# PMM_R_19.net
KiCad netlist of a schematic drawn in EAGLE
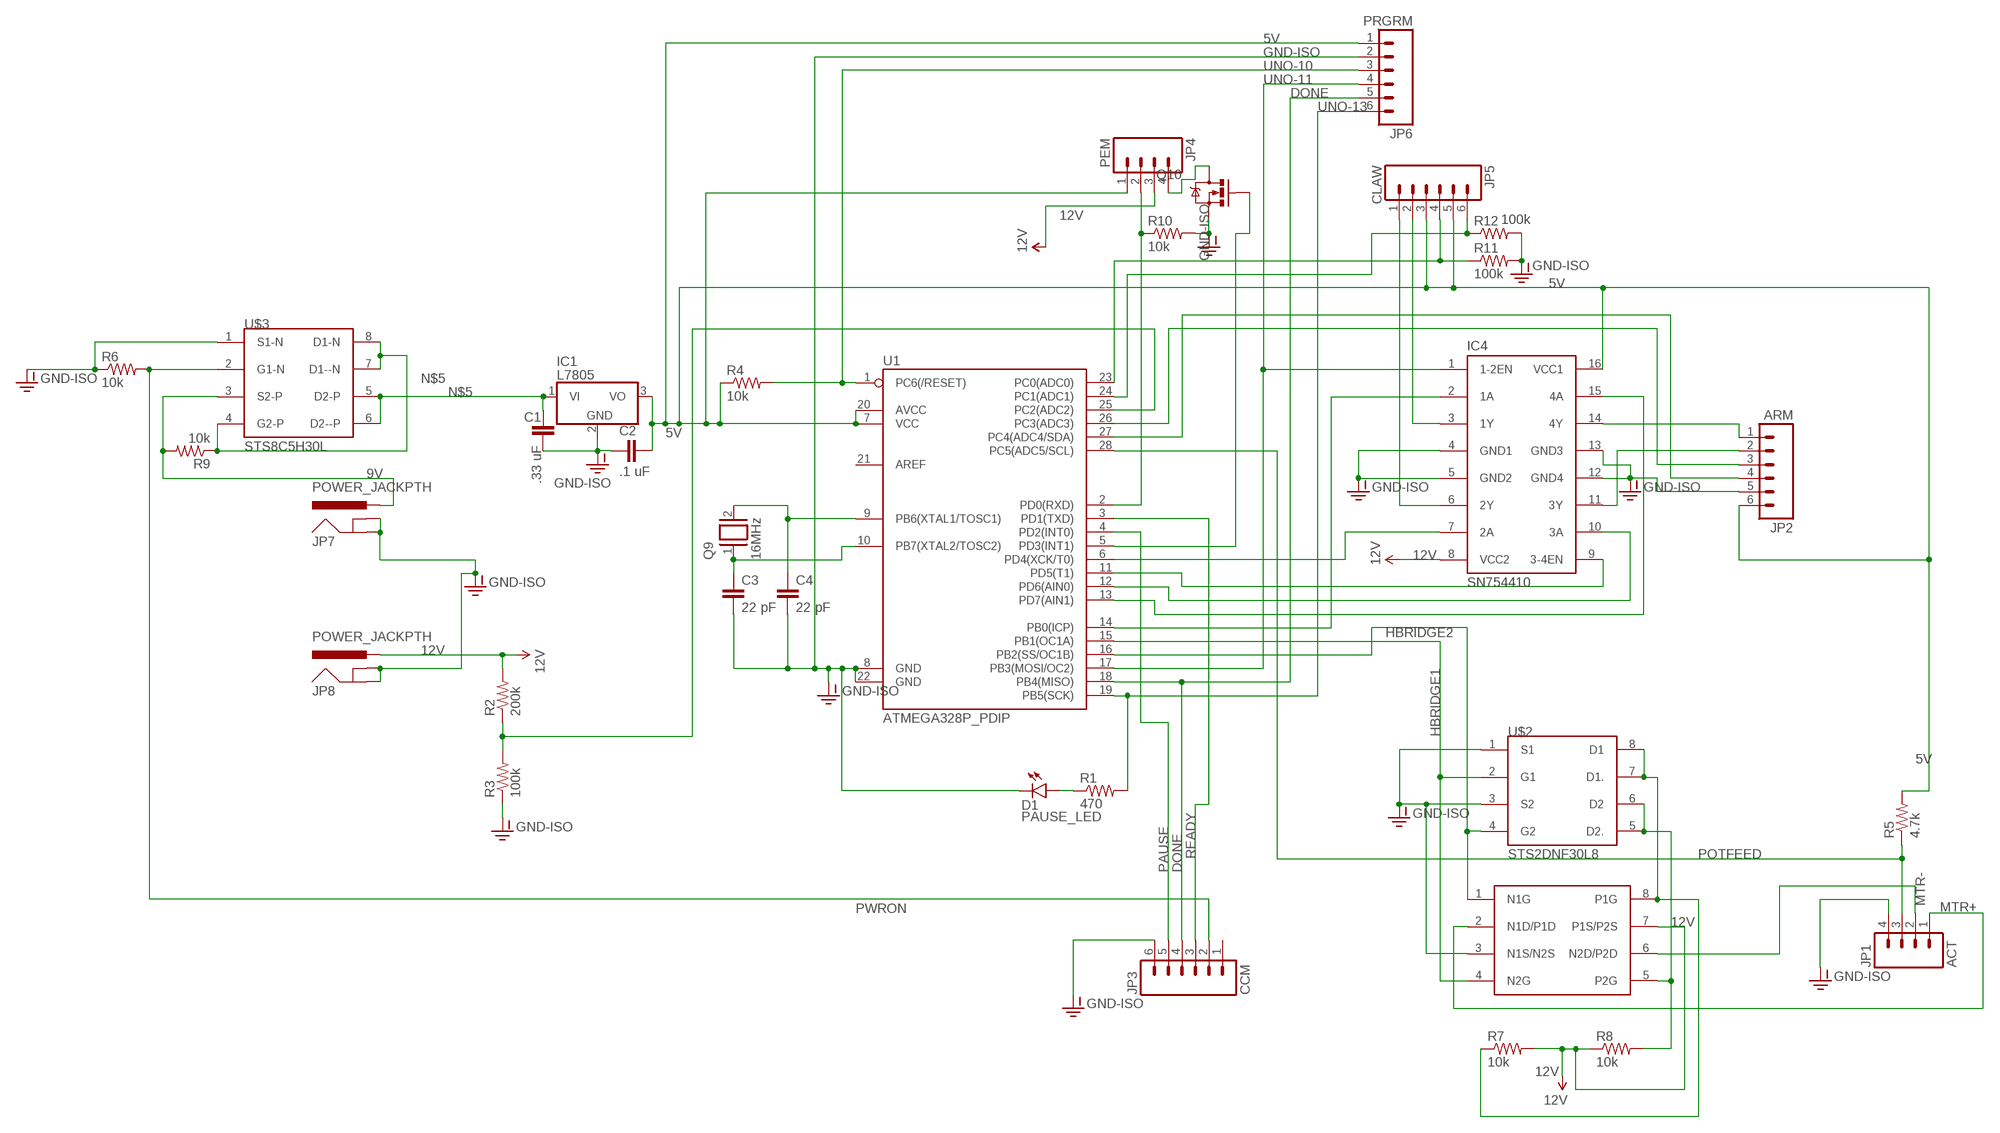
[diagram p0: schematic, sheet 1]

(export (version "E")
  (design (tool "Eeschema 10.0.6"))
  (components
    (comp (ref "C1")
      (value ".33 uF")
      (footprint "eagle-import:CAP-PTH-SMALL-KIT")
      (libsource (lib "eagle-import") (part "CAPKIT"))
    )
    (comp (ref "C2")
      (value ".1 uF")
      (footprint "eagle-import:CAP-PTH-SMALL-KIT")
      (libsource (lib "eagle-import") (part "CAPKIT"))
    )
    (comp (ref "C3")
      (value "22 pF")
      (footprint "eagle-import:C2.5-3")
      (libsource (lib "eagle-import") (part "C2,5-3"))
    )
    (comp (ref "C4")
      (value "22 pF")
      (footprint "eagle-import:C2.5-3")
      (libsource (lib "eagle-import") (part "C2,5-3"))
    )
    (comp (ref "D1")
      (value "PAUSE_LED")
      (footprint "eagle-import:LED5MM")
      (libsource (lib "eagle-import") (part "LED5MM"))
    )
    (comp (ref "DMHC3025LSD8")
      (value "DMHC3025LSD8")
      (footprint "eagle-import:SOIC-8")
      (libsource (lib "eagle-import") (part "DMHC3025LSD8"))
    )
    (comp (ref "IC1")
      (value "L7805")
      (footprint "eagle-import:TO220V")
      (libsource (lib "eagle-import") (part "78TV18"))
    )
    (comp (ref "IC4")
      (value "SN754410")
      (footprint "eagle-import:DIL16")
      (fields (field (name "MPN") "L293D"))
      (libsource (lib "eagle-import") (part "L293D"))
    )
    (comp (ref "JP1")
      (value "ACT")
      (footprint "eagle-import:1X04")
      (libsource (lib "eagle-import") (part "M04PTH"))
    )
    (comp (ref "JP2")
      (value "ARM")
      (footprint "eagle-import:1X06")
      (libsource (lib "eagle-import") (part "M06SILK_FEMALE_PTH"))
    )
    (comp (ref "JP3")
      (value "CCM")
      (footprint "eagle-import:1X06")
      (libsource (lib "eagle-import") (part "M06SILK_FEMALE_PTH"))
    )
    (comp (ref "JP4")
      (value "PEM")
      (footprint "eagle-import:1X04")
      (libsource (lib "eagle-import") (part "M04PTH"))
    )
    (comp (ref "JP5")
      (value "CLAW")
      (footprint "eagle-import:1X06")
      (libsource (lib "eagle-import") (part "M06SILK_FEMALE_PTH"))
    )
    (comp (ref "JP6")
      (value "PRGRM")
      (footprint "eagle-import:1X06")
      (libsource (lib "eagle-import") (part "M06SILK_FEMALE_PTH"))
    )
    (comp (ref "JP7")
      (value "POWER_JACKPTH")
      (footprint "eagle-import:POWER_JACK_PTH")
      (libsource (lib "eagle-import") (part "POWER_JACKPTH"))
    )
    (comp (ref "JP8")
      (value "POWER_JACKPTH")
      (footprint "eagle-import:POWER_JACK_PTH")
      (libsource (lib "eagle-import") (part "POWER_JACKPTH"))
    )
    (comp (ref "Q9")
      (value "16MHz")
      (footprint "eagle-import:QS")
      (libsource (lib "eagle-import") (part "XTAL/S"))
    )
    (comp (ref "Q10")
      (value "MOSFET-NCHANNELFQP30N06L")
      (footprint "eagle-import:TO220V")
      (libsource (lib "eagle-import") (part "MOSFET-NCHANNELFQP30N06L"))
    )
    (comp (ref "R1")
      (value "470")
      (footprint "eagle-import:1206")
      (libsource (lib "eagle-import") (part "RESISTOR1206"))
    )
    (comp (ref "R2")
      (value "200k")
      (footprint "eagle-import:1206")
      (libsource (lib "eagle-import") (part "RESISTOR1206"))
    )
    (comp (ref "R3")
      (value "100k")
      (footprint "eagle-import:1206")
      (libsource (lib "eagle-import") (part "RESISTOR1206"))
    )
    (comp (ref "R4")
      (value "10k")
      (footprint "eagle-import:1206")
      (libsource (lib "eagle-import") (part "RESISTOR1206"))
    )
    (comp (ref "R5")
      (value "4.7k")
      (footprint "eagle-import:1206")
      (libsource (lib "eagle-import") (part "RESISTOR1206"))
    )
    (comp (ref "R6")
      (value "10k")
      (footprint "eagle-import:1206")
      (libsource (lib "eagle-import") (part "RESISTOR1206"))
    )
    (comp (ref "R7")
      (value "10k")
      (footprint "eagle-import:1206")
      (libsource (lib "eagle-import") (part "RESISTOR1206"))
    )
    (comp (ref "R8")
      (value "10k")
      (footprint "eagle-import:1206")
      (libsource (lib "eagle-import") (part "RESISTOR1206"))
    )
    (comp (ref "R9")
      (value "10k")
      (footprint "eagle-import:1206")
      (libsource (lib "eagle-import") (part "RESISTOR1206"))
    )
    (comp (ref "R10")
      (value "10k")
      (footprint "eagle-import:1206")
      (libsource (lib "eagle-import") (part "RESISTOR1206"))
    )
    (comp (ref "R11")
      (value "100k")
      (footprint "eagle-import:1206")
      (libsource (lib "eagle-import") (part "RESISTOR1206"))
    )
    (comp (ref "R12")
      (value "100k")
      (footprint "eagle-import:1206")
      (libsource (lib "eagle-import") (part "RESISTOR1206"))
    )
    (comp (ref "U$2")
      (value "STS2DNF30L8")
      (footprint "eagle-import:SOIC-8")
      (libsource (lib "eagle-import") (part "STS2DNF30L8"))
    )
    (comp (ref "U$3")
      (value "STS8C5H30L")
      (footprint "eagle-import:SOIC-8")
      (libsource (lib "eagle-import") (part "STS8C5H30LSTS8C5H30L"))
    )
    (comp (ref "U1")
      (value "ATMEGA328P_PDIP")
      (footprint "eagle-import:DIL28-3")
      (libsource (lib "eagle-import") (part "ATMEGA328P_PDIP"))
    )
  )
  (nets
    (net (code "1") (name "/5V") (class "Default")
      (node (ref "C2") (pin "1") (pinfunction "1_1") (pintype "passive"))
      (node (ref "IC1") (pin "3") (pinfunction "VO_3") (pintype "passive"))
      (node (ref "IC4") (pin "16") (pinfunction "VCC1_16") (pintype "power_in"))
      (node (ref "JP2") (pin "6") (pinfunction "6_6") (pintype "passive"))
      (node (ref "JP4") (pin "1") (pinfunction "1_1") (pintype "passive"))
      (node (ref "JP5") (pin "3") (pinfunction "3_3") (pintype "passive"))
      (node (ref "JP5") (pin "5") (pinfunction "5_5") (pintype "passive"))
      (node (ref "JP6") (pin "1") (pinfunction "1_1") (pintype "passive"))
      (node (ref "R4") (pin "1") (pinfunction "1_1") (pintype "passive"))
      (node (ref "R5") (pin "2") (pinfunction "2_2") (pintype "passive"))
      (node (ref "U1") (pin "20") (pinfunction "AVCC_20") (pintype "bidirectional"))
      (node (ref "U1") (pin "7") (pinfunction "VCC_7") (pintype "bidirectional"))
    )
    (net (code "2") (name "/9V") (class "Default")
      (node (ref "JP7") (pin "PWR") (pinfunction "PWR_PWR") (pintype "bidirectional"))
      (node (ref "R9") (pin "2") (pinfunction "2_2") (pintype "passive"))
      (node (ref "U$3") (pin "3") (pinfunction "S2-P_3") (pintype "bidirectional"))
    )
    (net (code "3") (name "/DONE") (class "Default")
      (node (ref "JP3") (pin "4") (pinfunction "4_4") (pintype "passive"))
      (node (ref "JP6") (pin "5") (pinfunction "5_5") (pintype "passive"))
      (node (ref "U1") (pin "18") (pinfunction "PB4(MISO)_18") (pintype "bidirectional"))
    )
    (net (code "4") (name "/HBRIDGE1") (class "Default")
      (node (ref "DMHC3025LSD8") (pin "4") (pinfunction "N2G_4") (pintype "bidirectional"))
      (node (ref "U$2") (pin "2") (pinfunction "G1_2") (pintype "bidirectional"))
      (node (ref "U1") (pin "15") (pinfunction "PB1(OC1A)_15") (pintype "bidirectional"))
    )
    (net (code "5") (name "/HBRIDGE2") (class "Default")
      (node (ref "DMHC3025LSD8") (pin "1") (pinfunction "N1G_1") (pintype "bidirectional"))
      (node (ref "U$2") (pin "4") (pinfunction "G2_4") (pintype "bidirectional"))
      (node (ref "U1") (pin "16") (pinfunction "PB2(SS/OC1B)_16") (pintype "bidirectional"))
    )
    (net (code "6") (name "/MTR+") (class "Default")
      (node (ref "DMHC3025LSD8") (pin "2") (pinfunction "N1D/P1D_2") (pintype "bidirectional"))
      (node (ref "JP1") (pin "1") (pinfunction "1_1") (pintype "passive"))
    )
    (net (code "7") (name "/MTR-") (class "Default")
      (node (ref "DMHC3025LSD8") (pin "6") (pinfunction "N2D/P2D_6") (pintype "bidirectional"))
      (node (ref "JP1") (pin "2") (pinfunction "2_2") (pintype "passive"))
    )
    (net (code "8") (name "/N$5") (class "Default")
      (node (ref "C1") (pin "1") (pinfunction "1_1") (pintype "passive"))
      (node (ref "IC1") (pin "1") (pinfunction "VI_1") (pintype "input"))
      (node (ref "U$3") (pin "5") (pinfunction "D2-P_5") (pintype "bidirectional"))
      (node (ref "U$3") (pin "6") (pinfunction "D2--P_6") (pintype "bidirectional"))
    )
    (net (code "9") (name "/PAUSE") (class "Default")
      (node (ref "JP3") (pin "5") (pinfunction "5_5") (pintype "passive"))
      (node (ref "U1") (pin "4") (pinfunction "PD2(INT0)_4") (pintype "bidirectional"))
    )
    (net (code "10") (name "/POTFEED") (class "Default")
      (node (ref "JP1") (pin "3") (pinfunction "3_3") (pintype "passive"))
      (node (ref "R5") (pin "1") (pinfunction "1_1") (pintype "passive"))
      (node (ref "U1") (pin "28") (pinfunction "PC5(ADC5/SCL)_28") (pintype "bidirectional"))
    )
    (net (code "11") (name "/PWRON") (class "Default")
      (node (ref "JP3") (pin "2") (pinfunction "2_2") (pintype "passive"))
      (node (ref "R6") (pin "2") (pinfunction "2_2") (pintype "passive"))
      (node (ref "U$3") (pin "2") (pinfunction "G1-N_2") (pintype "bidirectional"))
    )
    (net (code "12") (name "/READY") (class "Default")
      (node (ref "JP3") (pin "3") (pinfunction "3_3") (pintype "passive"))
      (node (ref "U1") (pin "3") (pinfunction "PD1(TXD)_3") (pintype "bidirectional"))
    )
    (net (code "13") (name "/UNO-10") (class "Default")
      (node (ref "JP6") (pin "3") (pinfunction "3_3") (pintype "passive"))
      (node (ref "R4") (pin "2") (pinfunction "2_2") (pintype "passive"))
      (node (ref "U1") (pin "1") (pinfunction "PC6(/RESET)_1") (pintype "bidirectional"))
    )
    (net (code "14") (name "/UNO-11") (class "Default")
      (node (ref "IC4") (pin "1") (pinfunction "1-2EN_1") (pintype "input"))
      (node (ref "JP6") (pin "4") (pinfunction "4_4") (pintype "passive"))
      (node (ref "U1") (pin "17") (pinfunction "PB3(MOSI/OC2)_17") (pintype "bidirectional"))
    )
    (net (code "15") (name "/UNO-13") (class "Default")
      (node (ref "JP6") (pin "6") (pinfunction "6_6") (pintype "passive"))
      (node (ref "R1") (pin "2") (pinfunction "2_2") (pintype "passive"))
      (node (ref "U1") (pin "19") (pinfunction "PB5(SCK)_19") (pintype "bidirectional"))
    )
    (net (code "16") (name "12V") (class "Default")
      (node (ref "DMHC3025LSD8") (pin "7") (pinfunction "P1S/P2S_7") (pintype "bidirectional"))
      (node (ref "IC4") (pin "8") (pinfunction "VCC2_8") (pintype "power_in"))
      (node (ref "JP4") (pin "3") (pinfunction "3_3") (pintype "passive"))
      (node (ref "JP8") (pin "PWR") (pinfunction "PWR_PWR") (pintype "bidirectional"))
      (node (ref "R2") (pin "2") (pinfunction "2_2") (pintype "passive"))
      (node (ref "R7") (pin "2") (pinfunction "2_2") (pintype "passive"))
      (node (ref "R8") (pin "1") (pinfunction "1_1") (pintype "passive"))
    )
    (net (code "17") (name "GND-ISO") (class "Default")
      (node (ref "C1") (pin "2") (pinfunction "2_2") (pintype "passive"))
      (node (ref "C2") (pin "2") (pinfunction "2_2") (pintype "passive"))
      (node (ref "C3") (pin "2") (pinfunction "2_2") (pintype "passive"))
      (node (ref "C4") (pin "2") (pinfunction "2_2") (pintype "passive"))
      (node (ref "D1") (pin "K") (pinfunction "C_K") (pintype "passive"))
      (node (ref "DMHC3025LSD8") (pin "3") (pinfunction "N1S/N2S_3") (pintype "bidirectional"))
      (node (ref "IC1") (pin "2") (pinfunction "GND_2") (pintype "passive"))
      (node (ref "IC4") (pin "12") (pinfunction "GND4_12") (pintype "power_in"))
      (node (ref "IC4") (pin "13") (pinfunction "GND3_13") (pintype "power_in"))
      (node (ref "IC4") (pin "4") (pinfunction "GND1_4") (pintype "power_in"))
      (node (ref "IC4") (pin "5") (pinfunction "GND2_5") (pintype "power_in"))
      (node (ref "JP1") (pin "4") (pinfunction "4_4") (pintype "passive"))
      (node (ref "JP2") (pin "5") (pinfunction "5_5") (pintype "passive"))
      (node (ref "JP3") (pin "6") (pinfunction "6_6") (pintype "passive"))
      (node (ref "JP6") (pin "2") (pinfunction "2_2") (pintype "passive"))
      (node (ref "JP7") (pin "GND") (pinfunction "GND_GND") (pintype "bidirectional"))
      (node (ref "JP7") (pin "GNDBREAK") (pinfunction "GNDBREAK_GNDBREAK") (pintype "bidirectional"))
      (node (ref "JP8") (pin "GND") (pinfunction "GND_GND") (pintype "bidirectional"))
      (node (ref "JP8") (pin "GNDBREAK") (pinfunction "GNDBREAK_GNDBREAK") (pintype "bidirectional"))
      (node (ref "Q10") (pin "3") (pinfunction "S_3") (pintype "passive"))
      (node (ref "R10") (pin "2") (pinfunction "2_2") (pintype "passive"))
      (node (ref "R11") (pin "2") (pinfunction "2_2") (pintype "passive"))
      (node (ref "R12") (pin "2") (pinfunction "2_2") (pintype "passive"))
      (node (ref "R3") (pin "1") (pinfunction "1_1") (pintype "passive"))
      (node (ref "R6") (pin "1") (pinfunction "1_1") (pintype "passive"))
      (node (ref "U$2") (pin "1") (pinfunction "S1_1") (pintype "bidirectional"))
      (node (ref "U$2") (pin "3") (pinfunction "S2_3") (pintype "bidirectional"))
      (node (ref "U$3") (pin "1") (pinfunction "S1-N_1") (pintype "bidirectional"))
      (node (ref "U1") (pin "22") (pinfunction "GND_22") (pintype "bidirectional"))
      (node (ref "U1") (pin "8") (pinfunction "GND_8") (pintype "bidirectional"))
    )
    (net (code "18") (name "Net-(D1-PadA)") (class "Default")
      (node (ref "D1") (pin "A") (pinfunction "A_A") (pintype "passive"))
      (node (ref "R1") (pin "1") (pinfunction "1_1") (pintype "passive"))
    )
    (net (code "19") (name "Net-(DMHC3025LSD8-P1G)") (class "Default")
      (node (ref "DMHC3025LSD8") (pin "8") (pinfunction "P1G_8") (pintype "bidirectional"))
      (node (ref "R7") (pin "1") (pinfunction "1_1") (pintype "passive"))
      (node (ref "U$2") (pin "7") (pinfunction "D1._7") (pintype "bidirectional"))
      (node (ref "U$2") (pin "8") (pinfunction "D1_8") (pintype "bidirectional"))
    )
    (net (code "20") (name "Net-(DMHC3025LSD8-P2G)") (class "Default")
      (node (ref "DMHC3025LSD8") (pin "5") (pinfunction "P2G_5") (pintype "bidirectional"))
      (node (ref "R8") (pin "2") (pinfunction "2_2") (pintype "passive"))
      (node (ref "U$2") (pin "5") (pinfunction "D2._5") (pintype "bidirectional"))
      (node (ref "U$2") (pin "6") (pinfunction "D2_6") (pintype "bidirectional"))
    )
    (net (code "21") (name "Net-(IC4-1A)") (class "Default")
      (node (ref "IC4") (pin "2") (pinfunction "1A_2") (pintype "input"))
      (node (ref "U1") (pin "14") (pinfunction "PB0(ICP)_14") (pintype "bidirectional"))
    )
    (net (code "22") (name "Net-(IC4-1Y)") (class "Default")
      (node (ref "IC4") (pin "3") (pinfunction "1Y_3") (pintype "output"))
      (node (ref "JP5") (pin "2") (pinfunction "2_2") (pintype "passive"))
    )
    (net (code "23") (name "Net-(IC4-2A)") (class "Default")
      (node (ref "IC4") (pin "7") (pinfunction "2A_7") (pintype "input"))
      (node (ref "U1") (pin "6") (pinfunction "PD4(XCK/T0)_6") (pintype "bidirectional"))
    )
    (net (code "24") (name "Net-(IC4-2Y)") (class "Default")
      (node (ref "IC4") (pin "6") (pinfunction "2Y_6") (pintype "output"))
      (node (ref "JP5") (pin "1") (pinfunction "1_1") (pintype "passive"))
    )
    (net (code "25") (name "Net-(IC4-3-4EN)") (class "Default")
      (node (ref "IC4") (pin "9") (pinfunction "3-4EN_9") (pintype "input"))
      (node (ref "U1") (pin "11") (pinfunction "PD5(T1)_11") (pintype "bidirectional"))
    )
    (net (code "26") (name "Net-(IC4-3A)") (class "Default")
      (node (ref "IC4") (pin "10") (pinfunction "3A_10") (pintype "input"))
      (node (ref "U1") (pin "12") (pinfunction "PD6(AIN0)_12") (pintype "bidirectional"))
    )
    (net (code "27") (name "Net-(IC4-3Y)") (class "Default")
      (node (ref "IC4") (pin "11") (pinfunction "3Y_11") (pintype "output"))
      (node (ref "JP2") (pin "2") (pinfunction "2_2") (pintype "passive"))
    )
    (net (code "28") (name "Net-(IC4-4A)") (class "Default")
      (node (ref "IC4") (pin "15") (pinfunction "4A_15") (pintype "input"))
      (node (ref "U1") (pin "13") (pinfunction "PD7(AIN1)_13") (pintype "bidirectional"))
    )
    (net (code "29") (name "Net-(IC4-4Y)") (class "Default")
      (node (ref "IC4") (pin "14") (pinfunction "4Y_14") (pintype "output"))
      (node (ref "JP2") (pin "1") (pinfunction "1_1") (pintype "passive"))
    )
    (net (code "30") (name "Net-(Q10-D)") (class "Default")
      (node (ref "JP4") (pin "4") (pinfunction "4_4") (pintype "passive"))
      (node (ref "Q10") (pin "2") (pinfunction "D_2") (pintype "passive"))
    )
    (net (code "31") (name "Net-(Q10-G)") (class "Default")
      (node (ref "Q10") (pin "1") (pinfunction "G_1") (pintype "passive"))
      (node (ref "U1") (pin "5") (pinfunction "PD3(INT1)_5") (pintype "bidirectional"))
    )
    (net (code "32") (name "Net-(U$3-D1--N)") (class "Default")
      (node (ref "R9") (pin "1") (pinfunction "1_1") (pintype "passive"))
      (node (ref "U$3") (pin "4") (pinfunction "G2-P_4") (pintype "bidirectional"))
      (node (ref "U$3") (pin "7") (pinfunction "D1--N_7") (pintype "bidirectional"))
      (node (ref "U$3") (pin "8") (pinfunction "D1-N_8") (pintype "bidirectional"))
    )
    (net (code "33") (name "Net-(U1-PB6(XTAL1{slash}TOSC1))") (class "Default")
      (node (ref "C4") (pin "1") (pinfunction "1_1") (pintype "passive"))
      (node (ref "Q9") (pin "2") (pinfunction "2_2") (pintype "passive"))
      (node (ref "U1") (pin "9") (pinfunction "PB6(XTAL1/TOSC1)_9") (pintype "bidirectional"))
    )
    (net (code "34") (name "Net-(U1-PB7(XTAL2{slash}TOSC2))") (class "Default")
      (node (ref "C3") (pin "1") (pinfunction "1_1") (pintype "passive"))
      (node (ref "Q9") (pin "1") (pinfunction "1_1") (pintype "passive"))
      (node (ref "U1") (pin "10") (pinfunction "PB7(XTAL2/TOSC2)_10") (pintype "bidirectional"))
    )
    (net (code "35") (name "Net-(U1-PC0(ADC0))") (class "Default")
      (node (ref "JP5") (pin "4") (pinfunction "4_4") (pintype "passive"))
      (node (ref "R11") (pin "1") (pinfunction "1_1") (pintype "passive"))
      (node (ref "U1") (pin "23") (pinfunction "PC0(ADC0)_23") (pintype "bidirectional"))
    )
    (net (code "36") (name "Net-(U1-PC1(ADC1))") (class "Default")
      (node (ref "JP5") (pin "6") (pinfunction "6_6") (pintype "passive"))
      (node (ref "R12") (pin "1") (pinfunction "1_1") (pintype "passive"))
      (node (ref "U1") (pin "24") (pinfunction "PC1(ADC1)_24") (pintype "bidirectional"))
    )
    (net (code "37") (name "Net-(U1-PC2(ADC2))") (class "Default")
      (node (ref "R2") (pin "1") (pinfunction "1_1") (pintype "passive"))
      (node (ref "R3") (pin "2") (pinfunction "2_2") (pintype "passive"))
      (node (ref "U1") (pin "25") (pinfunction "PC2(ADC2)_25") (pintype "bidirectional"))
    )
    (net (code "38") (name "Net-(U1-PC3(ADC3))") (class "Default")
      (node (ref "JP2") (pin "3") (pinfunction "3_3") (pintype "passive"))
      (node (ref "U1") (pin "26") (pinfunction "PC3(ADC3)_26") (pintype "bidirectional"))
    )
    (net (code "39") (name "Net-(U1-PC4(ADC4{slash}SDA))") (class "Default")
      (node (ref "JP2") (pin "4") (pinfunction "4_4") (pintype "passive"))
      (node (ref "U1") (pin "27") (pinfunction "PC4(ADC4/SDA)_27") (pintype "bidirectional"))
    )
    (net (code "40") (name "Net-(U1-PD0(RXD))") (class "Default")
      (node (ref "JP4") (pin "2") (pinfunction "2_2") (pintype "passive"))
      (node (ref "R10") (pin "1") (pinfunction "1_1") (pintype "passive"))
      (node (ref "U1") (pin "2") (pinfunction "PD0(RXD)_2") (pintype "bidirectional"))
    )
    (net (code "41") (name "unconnected-(JP3-Pad1)") (class "Default")
      (node (ref "JP3") (pin "1") (pinfunction "1_1") (pintype "passive"))
    )
    (net (code "42") (name "unconnected-(U1-AREF-Pad21)") (class "Default")
      (node (ref "U1") (pin "21") (pinfunction "AREF_21") (pintype "bidirectional"))
    )
  )
)
